# Jacdac_3D_Magnetometer_Maker.net
KiCad netlist of a schematic drawn in EAGLE
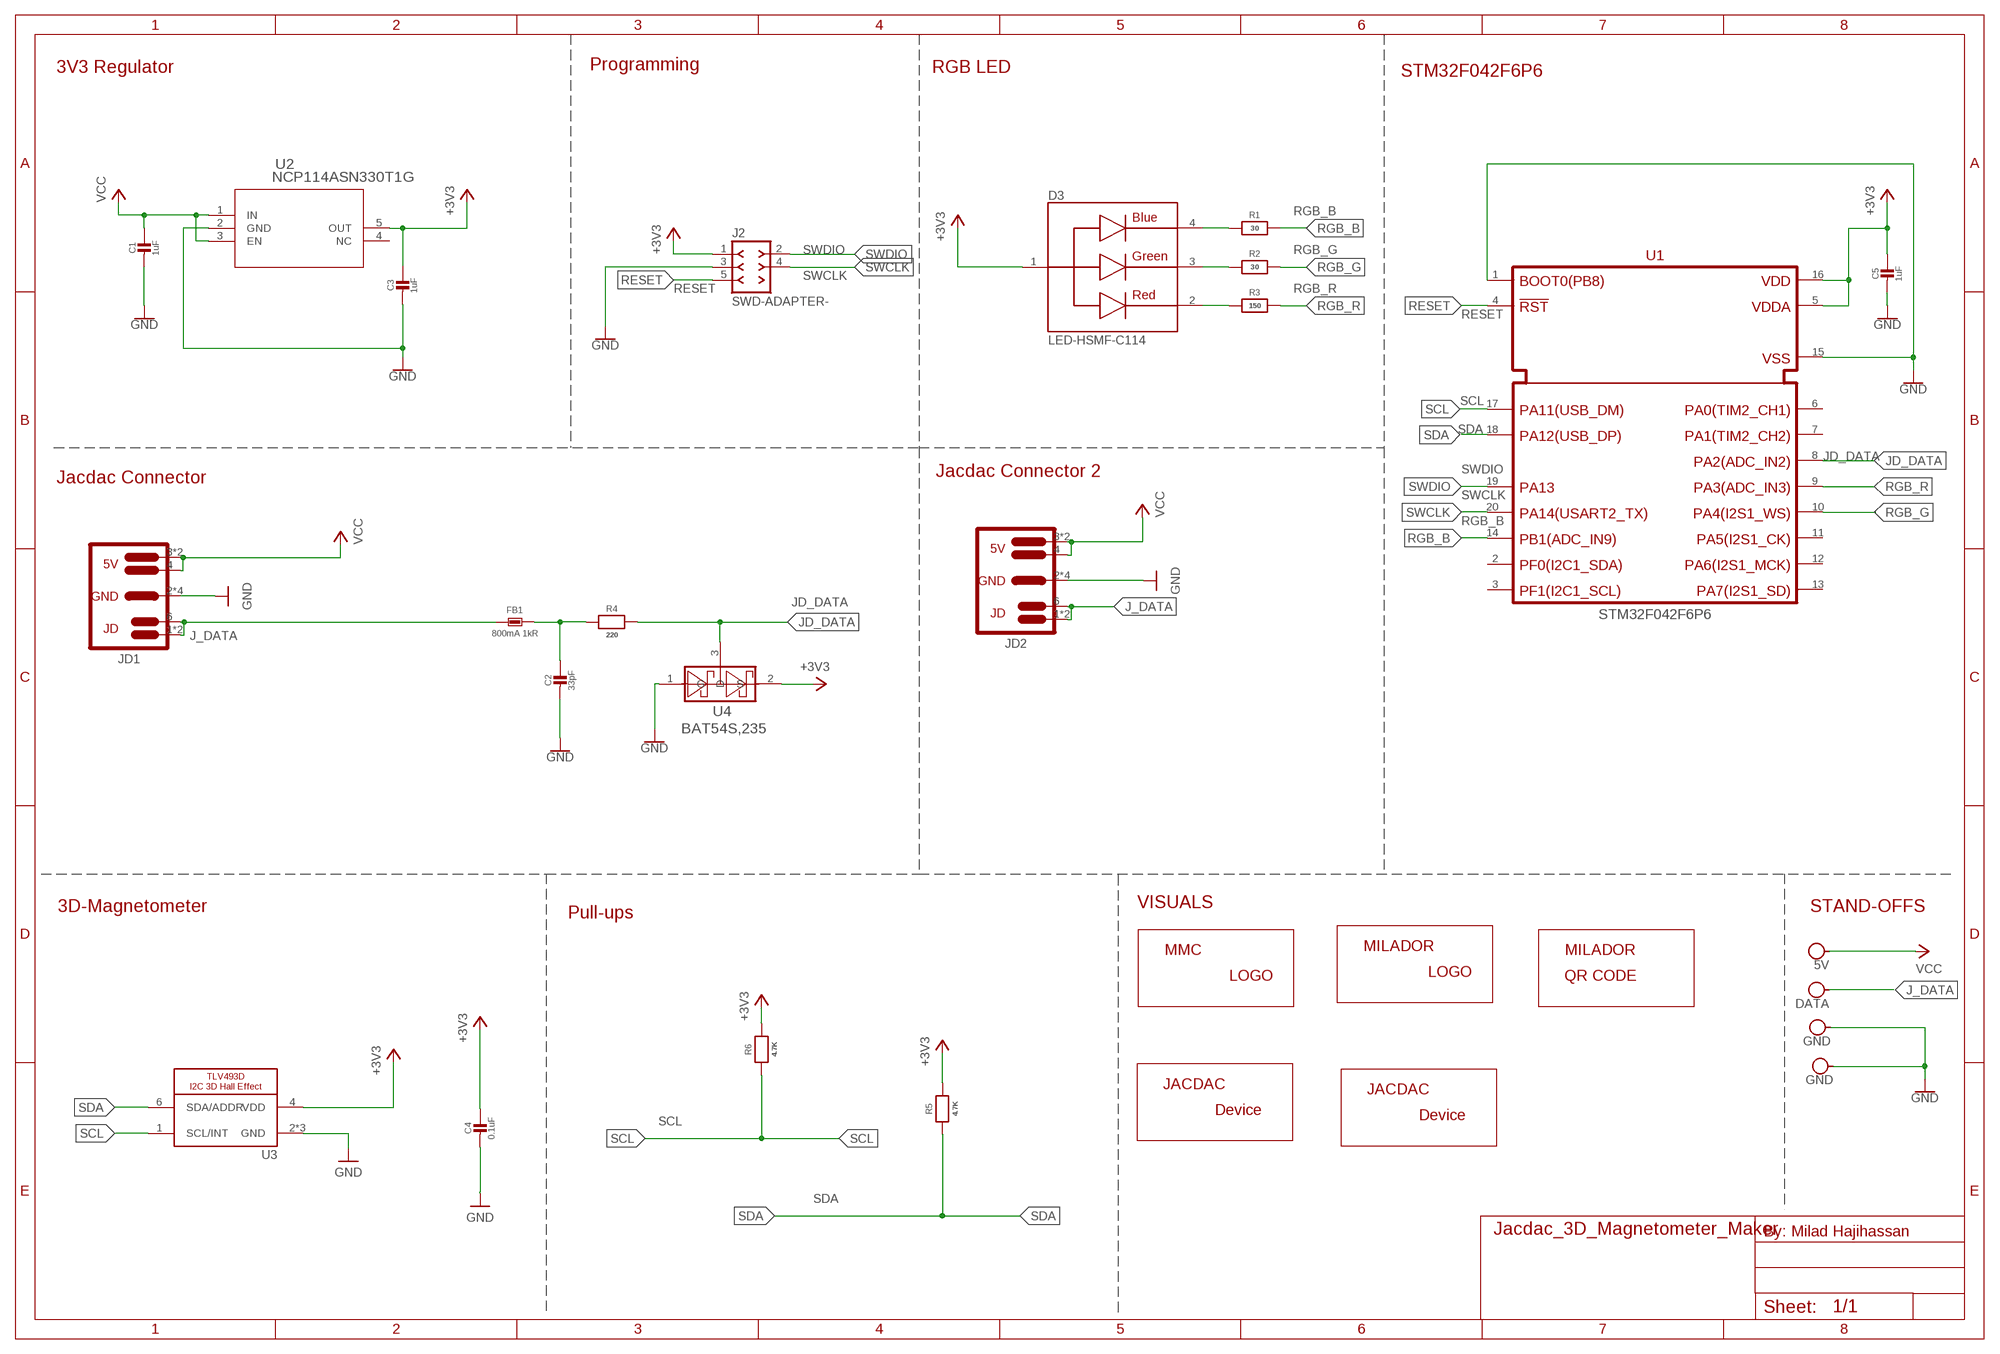
[diagram p0: schematic, sheet 1]

(export (version "E")
  (design (tool "Eeschema 10.0.6"))
  (components
    (comp (ref "C1")
      (value "1uF")
      (footprint "eagle-import:0603-NO")
      (libsource (lib "eagle-import") (part "CAP_CERAMIC-0603-NO"))
    )
    (comp (ref "C2")
      (value "33pF")
      (footprint "eagle-import:0603")
      (libsource (lib "eagle-import") (part "CAP_CERAMIC-0603"))
    )
    (comp (ref "C3")
      (value "1uF")
      (footprint "eagle-import:0603-NO")
      (libsource (lib "eagle-import") (part "CAP_CERAMIC-0603-NO"))
    )
    (comp (ref "C4")
      (value "0.1uF")
      (footprint "eagle-import:0603-NO")
      (libsource (lib "eagle-import") (part "CAP_CERAMIC-0603-NO"))
    )
    (comp (ref "C5")
      (value "1uF")
      (footprint "eagle-import:0603")
      (libsource (lib "eagle-import") (part "CAP_CERAMIC-0603"))
    )
    (comp (ref "D3")
      (value "LED-HSMF-C114")
      (footprint "eagle-import:DIOSC160X150X35-4N")
      (fields (field (name "MF") "Broadcom Limited") (field (name "MP") "HSMF-C114"))
      (libsource (lib "eagle-import") (part "LED-HSMF-C114"))
    )
    (comp (ref "FB1")
      (value "800mA 1kR")
      (footprint "eagle-import:0603-NO")
      (libsource (lib "eagle-import") (part "FERRITE-BEAD-0603-NO"))
    )
    (comp (ref "J2")
      (value "SWD-ADAPTER-")
      (footprint "eagle-import:SWD-ADAPTER")
      (libsource (lib "eagle-import") (part "SWD-ADAPTER-"))
    )
    (comp (ref "J3")
      (value "5V")
      (footprint "eagle-import:M3-HOLE-PWR-OUTL")
      (libsource (lib "eagle-import") (part "JACDAC-M3-PWR-OUTL"))
    )
    (comp (ref "J4")
      (value "DATA")
      (footprint "eagle-import:M3-HOLE-DATA-NOTCH")
      (libsource (lib "eagle-import") (part "JACDAC-M3-DATA-NOTCH"))
    )
    (comp (ref "J5")
      (value "GND")
      (footprint "eagle-import:M3-HOLE-GND")
      (libsource (lib "eagle-import") (part "JACDAC-M3-GND"))
    )
    (comp (ref "J6")
      (value "GND")
      (footprint "eagle-import:M3-HOLE-GND")
      (libsource (lib "eagle-import") (part "JACDAC-M3-GND"))
    )
    (comp (ref "JD1")
      (value "JACDAC-EDGE-OUTIE")
      (footprint "eagle-import:JD-EDGE-OUTIE")
      (libsource (lib "eagle-import") (part "JACDAC-EDGE-OUTIE"))
    )
    (comp (ref "JD2")
      (value "JACDAC-EDGE-OUTIE")
      (footprint "eagle-import:JD-EDGE-OUTIE")
      (libsource (lib "eagle-import") (part "JACDAC-EDGE-OUTIE"))
    )
    (comp (ref "LABEL_JACDAC_PS")
      (value "MILADOR-JACDAC-DEVICE-MAGNETOMETER")
      (footprint "eagle-import:JACDAC-3D-MAGNETOMETER")
      (libsource (lib "eagle-import") (part "MILADOR-JACDAC-DEVICE-MAGNETOMETER"))
    )
    (comp (ref "LABEL_MILADOR")
      (value "MILADOR-LOGO-")
      (footprint "eagle-import:MILADOR_LOGO1")
      (libsource (lib "eagle-import") (part "MILADOR-LOGO-"))
    )
    (comp (ref "LABEL_QR_CODE")
      (value "MILADOR-QR-CODE-JACDAC-MAGNETOMETER")
      (footprint "eagle-import:MILADOR_QR_JACDAC_MAGNETOMETER")
      (libsource (lib "eagle-import") (part "MILADOR-QR-CODE-JACDAC-MAGNETOMETER"))
    )
    (comp (ref "LABEL_TLV493D")
      (value "MILADOR-JACDAC-DEVICE-TLV493D")
      (footprint "eagle-import:JACDAC-TLV493D")
      (libsource (lib "eagle-import") (part "MILADOR-JACDAC-DEVICE-TLV493D"))
    )
    (comp (ref "MMC_LOGO")
      (value "MMC_LOGO-XSM")
      (footprint "eagle-import:MMC_X-SMALL_LOGO")
      (libsource (lib "eagle-import") (part "MMC_LOGO-XSM"))
    )
    (comp (ref "R1")
      (value "30")
      (footprint "eagle-import:0603")
      (libsource (lib "eagle-import") (part "RESISTOR-0603"))
    )
    (comp (ref "R2")
      (value "30")
      (footprint "eagle-import:0603")
      (libsource (lib "eagle-import") (part "RESISTOR-0603"))
    )
    (comp (ref "R3")
      (value "150")
      (footprint "eagle-import:0603")
      (libsource (lib "eagle-import") (part "RESISTOR-0603"))
    )
    (comp (ref "R4")
      (value "220")
      (footprint "eagle-import:0603")
      (libsource (lib "eagle-import") (part "RESISTOR-0603"))
    )
    (comp (ref "R5")
      (value "4.7K")
      (footprint "eagle-import:0603")
      (libsource (lib "eagle-import") (part "RESISTOR-0603"))
    )
    (comp (ref "R6")
      (value "4.7K")
      (footprint "eagle-import:0603")
      (libsource (lib "eagle-import") (part "RESISTOR-0603"))
    )
    (comp (ref "U1")
      (value "STM32F042F6P6")
      (footprint "eagle-import:TSSOP20")
      (libsource (lib "eagle-import") (part "STM32F042F6P6"))
    )
    (comp (ref "U2")
      (value "NCP114ASN330T1G")
      (footprint "eagle-import:TSOP-5_ONS")
      (fields (field (name "COPYRIGHT") "Copyright (C) 2021 Ultra Librarian. All rights reserved."))
      (libsource (lib "eagle-import") (part "NCP114ASN330T1G"))
    )
    (comp (ref "U3")
      (value "TLV493D")
      (footprint "eagle-import:SOT23-6")
      (libsource (lib "eagle-import") (part "TLV493D"))
    )
    (comp (ref "U4")
      (value "BAT54S,235")
      (footprint "eagle-import:SOT23-3")
      (fields (field (name "MF") "Diodes") (field (name "MP") "BSS138-7-F"))
      (libsource (lib "eagle-import") (part "BAT54S,235"))
    )
  )
  (nets
    (net (code "1") (name "+3V3") (class "Default")
      (node (ref "C3") (pin "1") (pinfunction "1_1") (pintype "passive"))
      (node (ref "C4") (pin "1") (pinfunction "1_1") (pintype "passive"))
      (node (ref "C5") (pin "1") (pinfunction "1_1") (pintype "passive"))
      (node (ref "D3") (pin "1") (pinfunction "1_1") (pintype "passive"))
      (node (ref "J2") (pin "1") (pinfunction "VCC_1_1") (pintype "passive"))
      (node (ref "R5") (pin "2") (pinfunction "2_2") (pintype "passive"))
      (node (ref "R6") (pin "2") (pinfunction "2_2") (pintype "passive"))
      (node (ref "U1") (pin "16") (pinfunction "VDD_16") (pintype "input"))
      (node (ref "U1") (pin "5") (pinfunction "VDDA_5") (pintype "input"))
      (node (ref "U2") (pin "5") (pinfunction "OUT_5") (pintype "power_in"))
      (node (ref "U3") (pin "4") (pinfunction "VDD_4") (pintype "power_in"))
      (node (ref "U4") (pin "2") (pinfunction "S_2") (pintype "passive"))
    )
    (net (code "2") (name "GND") (class "Default")
      (node (ref "C1") (pin "2") (pinfunction "2_2") (pintype "passive"))
      (node (ref "C2") (pin "2") (pinfunction "2_2") (pintype "passive"))
      (node (ref "C3") (pin "2") (pinfunction "2_2") (pintype "passive"))
      (node (ref "C4") (pin "2") (pinfunction "2_2") (pintype "passive"))
      (node (ref "C5") (pin "2") (pinfunction "2_2") (pintype "passive"))
      (node (ref "J2") (pin "3") (pinfunction "GND_3_3") (pintype "passive"))
      (node (ref "J5") (pin "H") (pinfunction "P$1_H") (pintype "bidirectional"))
      (node (ref "J6") (pin "H") (pinfunction "P$1_H") (pintype "bidirectional"))
      (node (ref "JD1") (pin "2") (pinfunction "1_2") (pintype "power_in"))
      (node (ref "JD1") (pin "5") (pinfunction "1_5") (pintype "power_in"))
      (node (ref "JD1") (pin "P$2") (pinfunction "1_P$2") (pintype "power_in"))
      (node (ref "JD1") (pin "P$4") (pinfunction "1_P$4") (pintype "power_in"))
      (node (ref "JD2") (pin "2") (pinfunction "1_2") (pintype "power_in"))
      (node (ref "JD2") (pin "5") (pinfunction "1_5") (pintype "power_in"))
      (node (ref "JD2") (pin "P$2") (pinfunction "1_P$2") (pintype "power_in"))
      (node (ref "JD2") (pin "P$4") (pinfunction "1_P$4") (pintype "power_in"))
      (node (ref "U1") (pin "1") (pinfunction "BOOT0_1") (pintype "input"))
      (node (ref "U1") (pin "15") (pinfunction "VSS_15") (pintype "input"))
      (node (ref "U2") (pin "2") (pinfunction "GND_2") (pintype "passive"))
      (node (ref "U3") (pin "2") (pinfunction "GND_2") (pintype "power_in"))
      (node (ref "U3") (pin "3") (pinfunction "GND_3") (pintype "power_in"))
      (node (ref "U3") (pin "5") (pinfunction "GND_5") (pintype "power_in"))
      (node (ref "U4") (pin "1") (pinfunction "G_1") (pintype "passive"))
    )
    (net (code "3") (name "JD_DATA") (class "Default")
      (node (ref "R4") (pin "2") (pinfunction "2_2") (pintype "passive"))
      (node (ref "U1") (pin "8") (pinfunction "PA2_8") (pintype "bidirectional"))
      (node (ref "U4") (pin "3") (pinfunction "D_3") (pintype "passive"))
    )
    (net (code "4") (name "J_DATA") (class "Default")
      (node (ref "FB1") (pin "2") (pinfunction "2_2") (pintype "passive"))
      (node (ref "J4") (pin "H") (pinfunction "P$1_H") (pintype "bidirectional"))
      (node (ref "JD1") (pin "1") (pinfunction "2_1") (pintype "bidirectional"))
      (node (ref "JD1") (pin "6") (pinfunction "6_6") (pintype "bidirectional"))
      (node (ref "JD1") (pin "P$3") (pinfunction "2_P$3") (pintype "bidirectional"))
      (node (ref "JD2") (pin "1") (pinfunction "2_1") (pintype "bidirectional"))
      (node (ref "JD2") (pin "6") (pinfunction "6_6") (pintype "bidirectional"))
      (node (ref "JD2") (pin "P$3") (pinfunction "2_P$3") (pintype "bidirectional"))
    )
    (net (code "5") (name "Net-(C2-Pad1)") (class "Default")
      (node (ref "C2") (pin "1") (pinfunction "1_1") (pintype "passive"))
      (node (ref "FB1") (pin "1") (pinfunction "1_1") (pintype "passive"))
      (node (ref "R4") (pin "1") (pinfunction "1_1") (pintype "passive"))
    )
    (net (code "6") (name "Net-(D3-Pad2)") (class "Default")
      (node (ref "D3") (pin "2") (pinfunction "2_2") (pintype "passive"))
      (node (ref "R3") (pin "1") (pinfunction "1_1") (pintype "passive"))
    )
    (net (code "7") (name "Net-(D3-Pad3)") (class "Default")
      (node (ref "D3") (pin "3") (pinfunction "3_3") (pintype "passive"))
      (node (ref "R2") (pin "1") (pinfunction "1_1") (pintype "passive"))
    )
    (net (code "8") (name "Net-(D3-Pad4)") (class "Default")
      (node (ref "D3") (pin "4") (pinfunction "4_4") (pintype "passive"))
      (node (ref "R1") (pin "1") (pinfunction "1_1") (pintype "passive"))
    )
    (net (code "9") (name "RESET") (class "Default")
      (node (ref "J2") (pin "5") (pinfunction "RESET_5_5") (pintype "passive"))
      (node (ref "U1") (pin "4") (pinfunction "~{RST}_4") (pintype "input"))
    )
    (net (code "10") (name "RGB_B") (class "Default")
      (node (ref "R1") (pin "2") (pinfunction "2_2") (pintype "passive"))
      (node (ref "U1") (pin "14") (pinfunction "PB1_14") (pintype "bidirectional"))
    )
    (net (code "11") (name "RGB_G") (class "Default")
      (node (ref "R2") (pin "2") (pinfunction "2_2") (pintype "passive"))
      (node (ref "U1") (pin "10") (pinfunction "PA4_10") (pintype "bidirectional"))
    )
    (net (code "12") (name "RGB_R") (class "Default")
      (node (ref "R3") (pin "2") (pinfunction "2_2") (pintype "passive"))
      (node (ref "U1") (pin "9") (pinfunction "PA3_9") (pintype "bidirectional"))
    )
    (net (code "13") (name "SCL") (class "Default")
      (node (ref "R6") (pin "1") (pinfunction "1_1") (pintype "passive"))
      (node (ref "U1") (pin "17") (pinfunction "PA11_17") (pintype "bidirectional"))
      (node (ref "U3") (pin "1") (pinfunction "SCL/INT_1") (pintype "bidirectional"))
    )
    (net (code "14") (name "SDA") (class "Default")
      (node (ref "R5") (pin "1") (pinfunction "1_1") (pintype "passive"))
      (node (ref "U1") (pin "18") (pinfunction "PA12_18") (pintype "bidirectional"))
      (node (ref "U3") (pin "6") (pinfunction "SDA/ADDR_6") (pintype "bidirectional"))
    )
    (net (code "15") (name "SWCLK") (class "Default")
      (node (ref "J2") (pin "4") (pinfunction "SWCLK_4_4") (pintype "passive"))
      (node (ref "U1") (pin "20") (pinfunction "PA14_20") (pintype "bidirectional"))
    )
    (net (code "16") (name "SWDIO") (class "Default")
      (node (ref "J2") (pin "2") (pinfunction "SWDIO_2_2") (pintype "passive"))
      (node (ref "U1") (pin "19") (pinfunction "PA13_19") (pintype "bidirectional"))
    )
    (net (code "17") (name "VCC") (class "Default")
      (node (ref "C1") (pin "1") (pinfunction "1_1") (pintype "passive"))
      (node (ref "J3") (pin "H") (pinfunction "P$1_H") (pintype "bidirectional"))
      (node (ref "JD1") (pin "3") (pinfunction "3_3") (pintype "power_in"))
      (node (ref "JD1") (pin "4") (pinfunction "4_4") (pintype "power_in"))
      (node (ref "JD1") (pin "P$1") (pinfunction "3_P$1") (pintype "power_in"))
      (node (ref "JD2") (pin "3") (pinfunction "3_3") (pintype "power_in"))
      (node (ref "JD2") (pin "4") (pinfunction "4_4") (pintype "power_in"))
      (node (ref "JD2") (pin "P$1") (pinfunction "3_P$1") (pintype "power_in"))
      (node (ref "U2") (pin "1") (pinfunction "IN_1") (pintype "input"))
      (node (ref "U2") (pin "3") (pinfunction "EN_3") (pintype "passive"))
    )
    (net (code "18") (name "unconnected-(U1-PA0-Pad6)") (class "Default")
      (node (ref "U1") (pin "6") (pinfunction "PA0_6") (pintype "bidirectional"))
    )
    (net (code "19") (name "unconnected-(U1-PA1-Pad7)") (class "Default")
      (node (ref "U1") (pin "7") (pinfunction "PA1_7") (pintype "bidirectional"))
    )
    (net (code "20") (name "unconnected-(U1-PA5-Pad11)") (class "Default")
      (node (ref "U1") (pin "11") (pinfunction "PA5_11") (pintype "bidirectional"))
    )
    (net (code "21") (name "unconnected-(U1-PA6-Pad12)") (class "Default")
      (node (ref "U1") (pin "12") (pinfunction "PA6_12") (pintype "bidirectional"))
    )
    (net (code "22") (name "unconnected-(U1-PA7-Pad13)") (class "Default")
      (node (ref "U1") (pin "13") (pinfunction "PA7_13") (pintype "bidirectional"))
    )
    (net (code "23") (name "unconnected-(U1-PF0-Pad2)") (class "Default")
      (node (ref "U1") (pin "2") (pinfunction "PF0_2") (pintype "bidirectional"))
    )
    (net (code "24") (name "unconnected-(U1-PF1-Pad3)") (class "Default")
      (node (ref "U1") (pin "3") (pinfunction "PF1_3") (pintype "bidirectional"))
    )
    (net (code "25") (name "unconnected-(U2-NC-Pad4)") (class "Default")
      (node (ref "U2") (pin "4") (pinfunction "NC_4") (pintype "no_connect"))
    )
  )
)
